# SensWear_Debug_UART2USB_1.net
KiCad netlist of a schematic drawn in Altium Designer
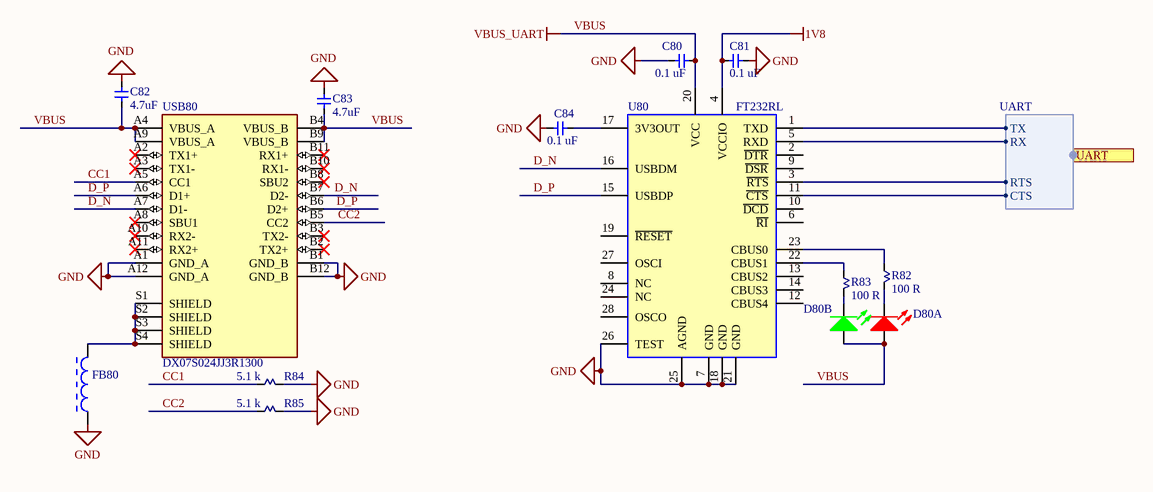
[diagram p0: SensWear_Debug_UART2USB_1.SchDoc]

(export (version "E")
  (design (tool "Eeschema 10.0.6"))
  (components
    (comp (ref "C80")
      (value "0.1 uF")
      (footprint "CAPC1005X05N")
      (description "CAP CER 0.1UF 16V X5R 0402")
      (fields
        (field (name "MANUFACTURER") "Murata Electronics")
        (field (name "MANUFACTURER PART NUMBER") "GRM155R61C104KA88D")
      )
      (libsource (lib "SensWearComponents") (part "GRM155R61C104KA88D__2"))
    )
    (comp (ref "C81")
      (value "0.1 uF")
      (footprint "CAPC1005X05N")
      (description "CAP CER 0.1UF 16V X5R 0402")
      (fields
        (field (name "MANUFACTURER") "Murata Electronics")
        (field (name "MANUFACTURER PART NUMBER") "GRM155R61C104KA88D")
      )
      (libsource (lib "SensWearComponents") (part "GRM155R61C104KA88D__2"))
    )
    (comp (ref "C82")
      (value "4.7uF")
      (footprint "CAPC1610X05N")
      (description "Cap Ceramic 4.7uF 10V X5R 10% Pad SMD 0603 85C T/R")
      (fields
        (field (name "MANUFACTURER") "Samsung")
        (field (name "MANUFACTURER PART NUMBER") "CL10A475KP8NNNC")
      )
      (libsource (lib "SensWearComponents") (part "CL10A475KP8NNNC"))
    )
    (comp (ref "C83")
      (value "4.7uF")
      (footprint "CAPC1610X05N")
      (description "Cap Ceramic 4.7uF 10V X5R 10% Pad SMD 0603 85C T/R")
      (fields
        (field (name "MANUFACTURER") "Samsung")
        (field (name "MANUFACTURER PART NUMBER") "CL10A475KP8NNNC")
      )
      (libsource (lib "SensWearComponents") (part "CL10A475KP8NNNC"))
    )
    (comp (ref "C84")
      (value "0.1 uF")
      (footprint "CAPC1005X05N")
      (description "CAP CER 0.1UF 16V X5R 0402")
      (fields
        (field (name "MANUFACTURER") "Murata Electronics")
        (field (name "MANUFACTURER PART NUMBER") "GRM155R61C104KA88D")
      )
      (libsource (lib "SensWearComponents") (part "GRM155R61C104KA88D__2"))
    )
    (comp (ref "D80")
      (value "LTST-C155KGJRKT")
      (footprint "LTST-C155KGJRKT")
      (description "LED GREEN/RED CLEAR CHIP SMD")
      (fields (field (name "MANUFACTURER") "Vishay Lite-On"))
      (libsource (lib "SensWearComponents") (part "LTST-C155KGJRKT"))
    )
    (comp (ref "FB80")
      (value "BLM15AG601SN1D")
      (footprint "MURA-BLM15-CHIP-2_V")
      (description "FERRITE BEAD 600 OHM 0402 1LN")
      (fields (field (name "MANUFACTURER") "Murata") (field (name "TOLERANCE") "25%"))
      (libsource (lib "SensWearComponents") (part "BLM15AG601SN1D"))
    )
    (comp (ref "R82")
      (value "100 R")
      (footprint "RESC1005X04N")
      (description "RES SMD 100 OHM 1% 1/10W 0402")
      (fields
        (field (name "MANUFACTURER") "Panasonic Electronic Components")
        (field (name "MANUFACTURER PART NUMBER") "ERJ-2RKF1000X")
      )
      (libsource (lib "SensWearComponents") (part "ERJ-2RKF1000X"))
    )
    (comp (ref "R83")
      (value "100 R")
      (footprint "RESC1005X04N")
      (description "RES SMD 100 OHM 1% 1/10W 0402")
      (fields
        (field (name "MANUFACTURER") "Panasonic Electronic Components")
        (field (name "MANUFACTURER PART NUMBER") "ERJ-2RKF1000X")
      )
      (libsource (lib "SensWearComponents") (part "ERJ-2RKF1000X"))
    )
    (comp (ref "R84")
      (value "5.1 k")
      (footprint "RESC1005X04N")
      (description "RES SMD 5.1K OHM 1% 1/10W 0402")
      (fields
        (field (name "MANUFACTURER") "Panasonic")
        (field (name "MANUFACTURER PART NUMBER") "ERJ-2RKF5101X")
      )
      (libsource (lib "SensWearComponents") (part "ERJ-2RKF5101X"))
    )
    (comp (ref "R85")
      (value "5.1 k")
      (footprint "RESC1005X04N")
      (description "RES SMD 5.1K OHM 1% 1/10W 0402")
      (fields
        (field (name "MANUFACTURER") "Panasonic")
        (field (name "MANUFACTURER PART NUMBER") "ERJ-2RKF5101X")
      )
      (libsource (lib "SensWearComponents") (part "ERJ-2RKF5101X"))
    )
    (comp (ref "U80")
      (value "FT232RL")
      (footprint "SOP65P780X200-28N")
      (description "IC USB FS SERIAL UART 28-SSOP")
      (fields
        (field (name "MANUFACTURER PART NUMBER") "FT232RL-REEL")
        (field (name "MANUFACTURER") "FTDI, Future Technology Devices International Ltd")
      )
      (libsource (lib "SensWearComponents") (part "FT232RL"))
    )
    (comp (ref "USB80")
      (value "DX07S024JJ3R1300")
      (footprint "JAE-DX07S024JJ3R1300-MFG")
      (description "Cut Tape - Usb Type C Receptacle Mid Mnt Dual R")
      (fields (field (name "MANUFACTURER") "JAE Electronics"))
      (libsource (lib "SensWearComponents") (part "DX07S024JJ3R1300"))
    )
  )
  (nets
    (net (code "2") (name "/CC1") (class "Default")
      (node (ref "R84") (pin "1") (pinfunction "1_1") (pintype "passive"))
      (node (ref "USB80") (pin "A5") (pinfunction "CC1_A5") (pintype "bidirectional"))
    )
    (net (code "3") (name "/CC2") (class "Default")
      (node (ref "R85") (pin "1") (pinfunction "1_1") (pintype "passive"))
      (node (ref "USB80") (pin "B5") (pinfunction "CC2_B5") (pintype "bidirectional"))
    )
    (net (code "4") (name "/CTS") (class "Default")
      (node (ref "U80") (pin "11") (pinfunction "~{CTS}_11") (pintype "passive"))
    )
    (net (code "5") (name "/D_N") (class "Default")
      (node (ref "U80") (pin "16") (pinfunction "USBDM_16") (pintype "passive"))
      (node (ref "USB80") (pin "A7") (pinfunction "D1-_A7") (pintype "bidirectional"))
      (node (ref "USB80") (pin "B7") (pinfunction "D2-_B7") (pintype "bidirectional"))
    )
    (net (code "6") (name "/D_P") (class "Default")
      (node (ref "U80") (pin "15") (pinfunction "USBDP_15") (pintype "passive"))
      (node (ref "USB80") (pin "A6") (pinfunction "D1+_A6") (pintype "bidirectional"))
      (node (ref "USB80") (pin "B6") (pinfunction "D2+_B6") (pintype "bidirectional"))
    )
    (net (code "7") (name "/RTS") (class "Default")
      (node (ref "U80") (pin "3") (pinfunction "~{RTS}_3") (pintype "passive"))
    )
    (net (code "8") (name "/RX") (class "Default")
      (node (ref "U80") (pin "5") (pinfunction "RXD_5") (pintype "passive"))
    )
    (net (code "9") (name "/TX") (class "Default")
      (node (ref "U80") (pin "1") (pinfunction "TXD_1") (pintype "passive"))
    )
    (net (code "11") (name "1V8") (class "Default")
      (node (ref "C81") (pin "2") (pinfunction "2_2") (pintype "passive"))
      (node (ref "U80") (pin "4") (pinfunction "VCCIO_4") (pintype "passive"))
    )
    (net (code "12") (name "GND") (class "Default")
      (node (ref "C80") (pin "2") (pinfunction "2_2") (pintype "passive"))
      (node (ref "C81") (pin "1") (pinfunction "1_1") (pintype "passive"))
      (node (ref "C82") (pin "1") (pinfunction "1_1") (pintype "passive"))
      (node (ref "C83") (pin "1") (pinfunction "1_1") (pintype "passive"))
      (node (ref "C84") (pin "2") (pinfunction "2_2") (pintype "passive"))
      (node (ref "FB80") (pin "1") (pinfunction "1_1") (pintype "passive"))
      (node (ref "R84") (pin "2") (pinfunction "2_2") (pintype "passive"))
      (node (ref "R85") (pin "2") (pinfunction "2_2") (pintype "passive"))
      (node (ref "U80") (pin "18") (pinfunction "GND_18") (pintype "passive"))
      (node (ref "U80") (pin "21") (pinfunction "GND_21") (pintype "passive"))
      (node (ref "U80") (pin "25") (pinfunction "AGND_25") (pintype "passive"))
      (node (ref "U80") (pin "26") (pinfunction "TEST_26") (pintype "passive"))
      (node (ref "U80") (pin "7") (pinfunction "GND_7") (pintype "passive"))
      (node (ref "USB80") (pin "A1") (pinfunction "GND_A_A1") (pintype "power_in"))
      (node (ref "USB80") (pin "A12") (pinfunction "GND_A_A12") (pintype "power_in"))
      (node (ref "USB80") (pin "B1") (pinfunction "GND_B_B1") (pintype "power_in"))
      (node (ref "USB80") (pin "B12") (pinfunction "GND_B_B12") (pintype "power_in"))
    )
    (net (code "13") (name "Net-(D80A-K)") (class "Default")
      (node (ref "D80") (pin "4") (pinfunction "K_4") (pintype "passive"))
      (node (ref "R82") (pin "1") (pinfunction "1_1") (pintype "passive"))
    )
    (net (code "14") (name "Net-(D80B-K)") (class "Default")
      (node (ref "D80") (pin "3") (pinfunction "K_3") (pintype "passive"))
      (node (ref "R83") (pin "1") (pinfunction "1_1") (pintype "passive"))
    )
    (net (code "15") (name "Net-(FB80-Pad2)") (class "Default")
      (node (ref "FB80") (pin "2") (pinfunction "2_2") (pintype "passive"))
      (node (ref "USB80") (pin "S1") (pinfunction "SHIELD_S1") (pintype "passive"))
      (node (ref "USB80") (pin "S2") (pinfunction "SHIELD_S2") (pintype "passive"))
      (node (ref "USB80") (pin "S3") (pinfunction "SHIELD_S3") (pintype "passive"))
      (node (ref "USB80") (pin "S4") (pinfunction "SHIELD_S4") (pintype "passive"))
    )
    (net (code "16") (name "Net-(U80-3V3OUT)") (class "Default")
      (node (ref "C84") (pin "1") (pinfunction "1_1") (pintype "passive"))
      (node (ref "U80") (pin "17") (pinfunction "3V3OUT_17") (pintype "passive"))
    )
    (net (code "17") (name "Net-(U80-CBUS0)") (class "Default")
      (node (ref "R82") (pin "2") (pinfunction "2_2") (pintype "passive"))
      (node (ref "U80") (pin "23") (pinfunction "CBUS0_23") (pintype "passive"))
    )
    (net (code "18") (name "Net-(U80-CBUS1)") (class "Default")
      (node (ref "R83") (pin "2") (pinfunction "2_2") (pintype "passive"))
      (node (ref "U80") (pin "22") (pinfunction "CBUS1_22") (pintype "passive"))
    )
    (net (code "19") (name "VBUS_UART") (class "Default")
      (node (ref "C80") (pin "1") (pinfunction "1_1") (pintype "passive"))
      (node (ref "C82") (pin "2") (pinfunction "2_2") (pintype "passive"))
      (node (ref "C83") (pin "2") (pinfunction "2_2") (pintype "passive"))
      (node (ref "D80") (pin "1") (pinfunction "A_1") (pintype "passive"))
      (node (ref "D80") (pin "2") (pinfunction "A_2") (pintype "passive"))
      (node (ref "U80") (pin "20") (pinfunction "VCC_20") (pintype "passive"))
      (node (ref "USB80") (pin "A4") (pinfunction "VBUS_A_A4") (pintype "passive"))
      (node (ref "USB80") (pin "A9") (pinfunction "VBUS_A_A9") (pintype "passive"))
      (node (ref "USB80") (pin "B4") (pinfunction "VBUS_B_B4") (pintype "passive"))
      (node (ref "USB80") (pin "B9") (pinfunction "VBUS_B_B9") (pintype "passive"))
    )
    (net (code "20") (name "unconnected-(U80-CBUS2-Pad13)") (class "Default")
      (node (ref "U80") (pin "13") (pinfunction "CBUS2_13") (pintype "passive"))
    )
    (net (code "21") (name "unconnected-(U80-CBUS3-Pad14)") (class "Default")
      (node (ref "U80") (pin "14") (pinfunction "CBUS3_14") (pintype "passive"))
    )
    (net (code "22") (name "unconnected-(U80-CBUS4-Pad12)") (class "Default")
      (node (ref "U80") (pin "12") (pinfunction "CBUS4_12") (pintype "passive"))
    )
    (net (code "23") (name "unconnected-(U80-NC-Pad8)") (class "Default")
      (node (ref "U80") (pin "8") (pinfunction "NC_8") (pintype "passive"))
    )
    (net (code "24") (name "unconnected-(U80-NC-Pad24)") (class "Default")
      (node (ref "U80") (pin "24") (pinfunction "NC_24") (pintype "passive"))
    )
    (net (code "25") (name "unconnected-(U80-OSCI-Pad27)") (class "Default")
      (node (ref "U80") (pin "27") (pinfunction "OSCI_27") (pintype "passive"))
    )
    (net (code "26") (name "unconnected-(U80-OSCO-Pad28)") (class "Default")
      (node (ref "U80") (pin "28") (pinfunction "OSCO_28") (pintype "passive"))
    )
    (net (code "27") (name "unconnected-(U80-~{DCD}-Pad10)") (class "Default")
      (node (ref "U80") (pin "10") (pinfunction "~{DCD}_10") (pintype "passive"))
    )
    (net (code "28") (name "unconnected-(U80-~{DSR}-Pad9)") (class "Default")
      (node (ref "U80") (pin "9") (pinfunction "~{DSR}_9") (pintype "passive"))
    )
    (net (code "29") (name "unconnected-(U80-~{DTR}-Pad2)") (class "Default")
      (node (ref "U80") (pin "2") (pinfunction "~{DTR}_2") (pintype "passive"))
    )
    (net (code "30") (name "unconnected-(U80-~{RESET}-Pad19)") (class "Default")
      (node (ref "U80") (pin "19") (pinfunction "~{RESET}_19") (pintype "passive"))
    )
    (net (code "31") (name "unconnected-(U80-~{RI}-Pad6)") (class "Default")
      (node (ref "U80") (pin "6") (pinfunction "~{RI}_6") (pintype "passive"))
    )
    (net (code "32") (name "unconnected-(USB80-RX1+-PadB11)") (class "Default")
      (node (ref "USB80") (pin "B11") (pinfunction "RX1+_B11") (pintype "bidirectional+no_connect"))
    )
    (net (code "33") (name "unconnected-(USB80-RX1--PadB10)") (class "Default")
      (node (ref "USB80") (pin "B10") (pinfunction "RX1-_B10") (pintype "bidirectional+no_connect"))
    )
    (net (code "34") (name "unconnected-(USB80-RX2+-PadA11)") (class "Default")
      (node (ref "USB80") (pin "A11") (pinfunction "RX2+_A11") (pintype "bidirectional+no_connect"))
    )
    (net (code "35") (name "unconnected-(USB80-RX2--PadA10)") (class "Default")
      (node (ref "USB80") (pin "A10") (pinfunction "RX2-_A10") (pintype "bidirectional+no_connect"))
    )
    (net (code "36") (name "unconnected-(USB80-SBU1-PadA8)") (class "Default")
      (node (ref "USB80") (pin "A8") (pinfunction "SBU1_A8") (pintype "bidirectional+no_connect"))
    )
    (net (code "37") (name "unconnected-(USB80-SBU2-PadB8)") (class "Default")
      (node (ref "USB80") (pin "B8") (pinfunction "SBU2_B8") (pintype "bidirectional+no_connect"))
    )
    (net (code "38") (name "unconnected-(USB80-TX1+-PadA2)") (class "Default")
      (node (ref "USB80") (pin "A2") (pinfunction "TX1+_A2") (pintype "bidirectional+no_connect"))
    )
    (net (code "39") (name "unconnected-(USB80-TX1--PadA3)") (class "Default")
      (node (ref "USB80") (pin "A3") (pinfunction "TX1-_A3") (pintype "bidirectional+no_connect"))
    )
    (net (code "40") (name "unconnected-(USB80-TX2+-PadB2)") (class "Default")
      (node (ref "USB80") (pin "B2") (pinfunction "TX2+_B2") (pintype "bidirectional+no_connect"))
    )
    (net (code "41") (name "unconnected-(USB80-TX2--PadB3)") (class "Default")
      (node (ref "USB80") (pin "B3") (pinfunction "TX2-_B3") (pintype "bidirectional+no_connect"))
    )
  )
)
